# datalogger.net
KiCad netlist of a schematic drawn in Altium Designer
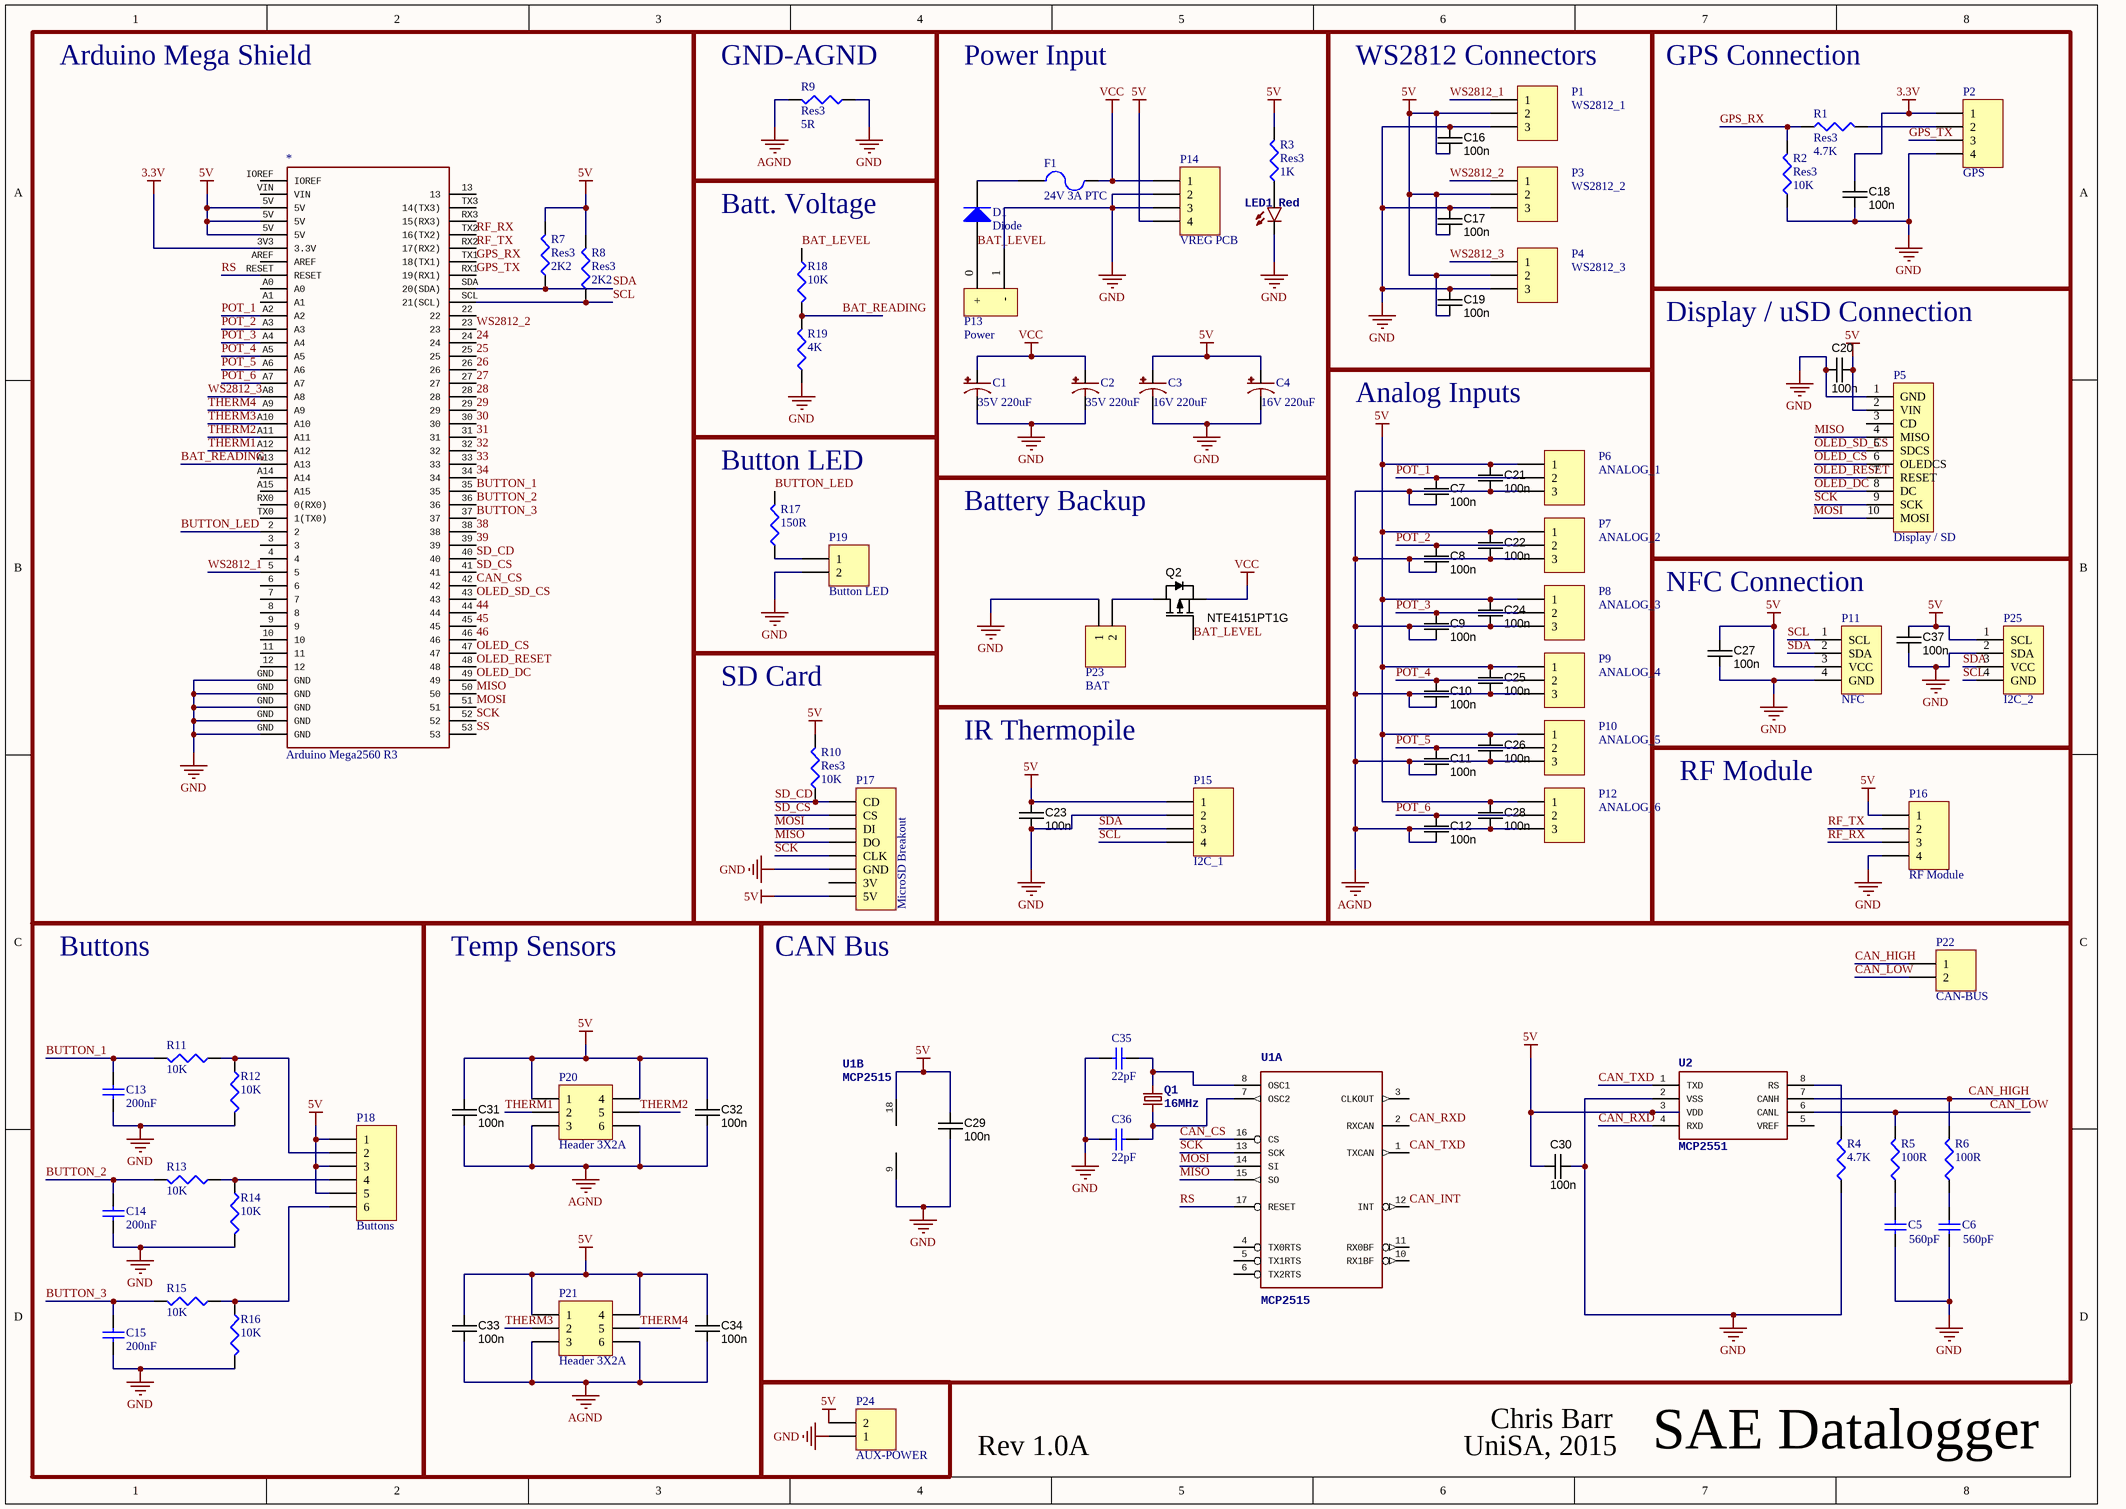
[diagram p0: datalogger.SchDoc]

(export (version "E")
  (design (tool "Eeschema 10.0.6"))
  (components
    (comp (ref "*")
      (value "Arduino Mega2560 R3")
      (footprint "Arduino Mega Shield - No Text")
      (libsource (lib "Schlib1") (part "Arduino Mega2560 R3"))
    )
    (comp (ref "C1")
      (value "35V 220uF")
      (footprint "8-DIA-CAP-3.5mm-Leads")
      (libsource (lib "Schlib1") (part "Capacitor 50V 470uF"))
    )
    (comp (ref "C2")
      (value "35V 220uF")
      (footprint "8-DIA-CAP-3.5mm-Leads")
      (libsource (lib "Schlib1") (part "Capacitor 50V 470uF"))
    )
    (comp (ref "C3")
      (value "16V 220uF")
      (footprint "6.3-DIA-CAP")
      (libsource (lib "Schlib1") (part "Capacitor 50V 470uF"))
    )
    (comp (ref "C4")
      (value "16V 220uF")
      (footprint "6.3-DIA-CAP")
      (libsource (lib "Schlib1") (part "Capacitor 50V 470uF"))
    )
    (comp (ref "C5")
      (value "560pF")
      (footprint "1608[0603]")
      (description "Capacitor (Semiconductor SIM Model)")
      (fields (field (name "Comment") "Cap Ceramic") (field (name "PUBLISHER") "Altium Limited"))
      (libsource (lib "Miscellaneous Devices") (part "Cap Semi"))
    )
    (comp (ref "C6")
      (value "560pF")
      (footprint "1608[0603]")
      (description "Capacitor (Semiconductor SIM Model)")
      (fields (field (name "Comment") "Cap Ceramic") (field (name "PUBLISHER") "Altium Limited"))
      (libsource (lib "Miscellaneous Devices") (part "Cap Semi"))
    )
    (comp (ref "C7")
      (value "100n")
      (footprint "CAPC1608X90N")
      (description "Capacitor SMD Cer 100nF 10% 50V X7R 0603")
      (fields (field (name "TOLERANCE") "±10%") (field (name "Comment") "approved sub OK"))
      (libsource (lib "PBL - Capacitors") (part "CAPC_100n_0603_X7R_50V_10%"))
    )
    (comp (ref "C8")
      (value "100n")
      (footprint "CAPC1608X90N")
      (description "Capacitor SMD Cer 100nF 10% 50V X7R 0603")
      (fields (field (name "TOLERANCE") "±10%") (field (name "Comment") "approved sub OK"))
      (libsource (lib "PBL - Capacitors") (part "CAPC_100n_0603_X7R_50V_10%"))
    )
    (comp (ref "C9")
      (value "100n")
      (footprint "CAPC1608X90N")
      (description "Capacitor SMD Cer 100nF 10% 50V X7R 0603")
      (fields (field (name "TOLERANCE") "±10%") (field (name "Comment") "approved sub OK"))
      (libsource (lib "PBL - Capacitors") (part "CAPC_100n_0603_X7R_50V_10%"))
    )
    (comp (ref "C10")
      (value "100n")
      (footprint "CAPC1608X90N")
      (description "Capacitor SMD Cer 100nF 10% 50V X7R 0603")
      (fields (field (name "TOLERANCE") "±10%") (field (name "Comment") "approved sub OK"))
      (libsource (lib "PBL - Capacitors") (part "CAPC_100n_0603_X7R_50V_10%"))
    )
    (comp (ref "C11")
      (value "100n")
      (footprint "CAPC1608X90N")
      (description "Capacitor SMD Cer 100nF 10% 50V X7R 0603")
      (fields (field (name "TOLERANCE") "±10%") (field (name "Comment") "approved sub OK"))
      (libsource (lib "PBL - Capacitors") (part "CAPC_100n_0603_X7R_50V_10%"))
    )
    (comp (ref "C12")
      (value "100n")
      (footprint "CAPC1608X90N")
      (description "Capacitor SMD Cer 100nF 10% 50V X7R 0603")
      (fields (field (name "TOLERANCE") "±10%") (field (name "Comment") "approved sub OK"))
      (libsource (lib "PBL - Capacitors") (part "CAPC_100n_0603_X7R_50V_10%"))
    )
    (comp (ref "C13")
      (value "200nF")
      (footprint "1608[0603]")
      (description "Capacitor (Semiconductor SIM Model)")
      (fields (field (name "Comment") "Cap Ceramic") (field (name "PUBLISHER") "Altium Limited"))
      (libsource (lib "Miscellaneous Devices") (part "Cap Semi"))
    )
    (comp (ref "C14")
      (value "200nF")
      (footprint "1608[0603]")
      (description "Capacitor (Semiconductor SIM Model)")
      (fields (field (name "Comment") "Cap Ceramic") (field (name "PUBLISHER") "Altium Limited"))
      (libsource (lib "Miscellaneous Devices") (part "Cap Semi"))
    )
    (comp (ref "C15")
      (value "200nF")
      (footprint "1608[0603]")
      (description "Capacitor (Semiconductor SIM Model)")
      (fields (field (name "Comment") "Cap Ceramic") (field (name "PUBLISHER") "Altium Limited"))
      (libsource (lib "Miscellaneous Devices") (part "Cap Semi"))
    )
    (comp (ref "C16")
      (value "100n")
      (footprint "CAPC1608X90N")
      (description "Capacitor SMD Cer 100nF 10% 50V X7R 0603")
      (fields (field (name "TOLERANCE") "±10%") (field (name "Comment") "approved sub OK"))
      (libsource (lib "PBL - Capacitors") (part "CAPC_100n_0603_X7R_50V_10%"))
    )
    (comp (ref "C17")
      (value "100n")
      (footprint "CAPC1608X90N")
      (description "Capacitor SMD Cer 100nF 10% 50V X7R 0603")
      (fields (field (name "TOLERANCE") "±10%") (field (name "Comment") "approved sub OK"))
      (libsource (lib "PBL - Capacitors") (part "CAPC_100n_0603_X7R_50V_10%"))
    )
    (comp (ref "C18")
      (value "100n")
      (footprint "CAPC1608X90N")
      (description "Capacitor SMD Cer 100nF 10% 50V X7R 0603")
      (fields (field (name "TOLERANCE") "±10%") (field (name "Comment") "approved sub OK"))
      (libsource (lib "PBL - Capacitors") (part "CAPC_100n_0603_X7R_50V_10%"))
    )
    (comp (ref "C19")
      (value "100n")
      (footprint "CAPC1608X90N")
      (description "Capacitor SMD Cer 100nF 10% 50V X7R 0603")
      (fields (field (name "TOLERANCE") "±10%") (field (name "Comment") "approved sub OK"))
      (libsource (lib "PBL - Capacitors") (part "CAPC_100n_0603_X7R_50V_10%"))
    )
    (comp (ref "C20")
      (value "100n")
      (footprint "CAPC1608X90N")
      (description "Capacitor SMD Cer 100nF 10% 50V X7R 0603")
      (fields (field (name "TOLERANCE") "±10%") (field (name "Comment") "approved sub OK"))
      (libsource (lib "PBL - Capacitors") (part "CAPC_100n_0603_X7R_50V_10%"))
    )
    (comp (ref "C21")
      (value "100n")
      (footprint "CAPC1608X90N")
      (description "Capacitor SMD Cer 100nF 10% 50V X7R 0603")
      (fields (field (name "TOLERANCE") "±10%") (field (name "Comment") "approved sub OK"))
      (libsource (lib "PBL - Capacitors") (part "CAPC_100n_0603_X7R_50V_10%"))
    )
    (comp (ref "C22")
      (value "100n")
      (footprint "CAPC1608X90N")
      (description "Capacitor SMD Cer 100nF 10% 50V X7R 0603")
      (fields (field (name "TOLERANCE") "±10%") (field (name "Comment") "approved sub OK"))
      (libsource (lib "PBL - Capacitors") (part "CAPC_100n_0603_X7R_50V_10%"))
    )
    (comp (ref "C23")
      (value "100n")
      (footprint "CAPC1608X90N")
      (description "Capacitor SMD Cer 100nF 10% 50V X7R 0603")
      (fields (field (name "TOLERANCE") "±10%") (field (name "Comment") "approved sub OK"))
      (libsource (lib "PBL - Capacitors") (part "CAPC_100n_0603_X7R_50V_10%"))
    )
    (comp (ref "C24")
      (value "100n")
      (footprint "CAPC1608X90N")
      (description "Capacitor SMD Cer 100nF 10% 50V X7R 0603")
      (fields (field (name "TOLERANCE") "±10%") (field (name "Comment") "approved sub OK"))
      (libsource (lib "PBL - Capacitors") (part "CAPC_100n_0603_X7R_50V_10%"))
    )
    (comp (ref "C25")
      (value "100n")
      (footprint "CAPC1608X90N")
      (description "Capacitor SMD Cer 100nF 10% 50V X7R 0603")
      (fields (field (name "TOLERANCE") "±10%") (field (name "Comment") "approved sub OK"))
      (libsource (lib "PBL - Capacitors") (part "CAPC_100n_0603_X7R_50V_10%"))
    )
    (comp (ref "C26")
      (value "100n")
      (footprint "CAPC1608X90N")
      (description "Capacitor SMD Cer 100nF 10% 50V X7R 0603")
      (fields (field (name "TOLERANCE") "±10%") (field (name "Comment") "approved sub OK"))
      (libsource (lib "PBL - Capacitors") (part "CAPC_100n_0603_X7R_50V_10%"))
    )
    (comp (ref "C27")
      (value "100n")
      (footprint "CAPC1608X90N")
      (description "Capacitor SMD Cer 100nF 10% 50V X7R 0603")
      (fields (field (name "TOLERANCE") "±10%") (field (name "Comment") "approved sub OK"))
      (libsource (lib "PBL - Capacitors") (part "CAPC_100n_0603_X7R_50V_10%"))
    )
    (comp (ref "C28")
      (value "100n")
      (footprint "CAPC1608X90N")
      (description "Capacitor SMD Cer 100nF 10% 50V X7R 0603")
      (fields (field (name "TOLERANCE") "±10%") (field (name "Comment") "approved sub OK"))
      (libsource (lib "PBL - Capacitors") (part "CAPC_100n_0603_X7R_50V_10%"))
    )
    (comp (ref "C29")
      (value "100n")
      (footprint "CAPC1608X90N")
      (description "Capacitor SMD Cer 100nF 10% 50V X7R 0603")
      (fields (field (name "TOLERANCE") "±10%") (field (name "Comment") "approved sub OK"))
      (libsource (lib "PBL - Capacitors") (part "CAPC_100n_0603_X7R_50V_10%"))
    )
    (comp (ref "C30")
      (value "100n")
      (footprint "CAPC1608X90N")
      (description "Capacitor SMD Cer 100nF 10% 50V X7R 0603")
      (fields (field (name "TOLERANCE") "±10%") (field (name "Comment") "approved sub OK"))
      (libsource (lib "PBL - Capacitors") (part "CAPC_100n_0603_X7R_50V_10%"))
    )
    (comp (ref "C31")
      (value "100n")
      (footprint "CAPC1608X90N")
      (description "Capacitor SMD Cer 100nF 10% 50V X7R 0603")
      (fields (field (name "TOLERANCE") "±10%") (field (name "Comment") "approved sub OK"))
      (libsource (lib "PBL - Capacitors") (part "CAPC_100n_0603_X7R_50V_10%"))
    )
    (comp (ref "C32")
      (value "100n")
      (footprint "CAPC1608X90N")
      (description "Capacitor SMD Cer 100nF 10% 50V X7R 0603")
      (fields (field (name "TOLERANCE") "±10%") (field (name "Comment") "approved sub OK"))
      (libsource (lib "PBL - Capacitors") (part "CAPC_100n_0603_X7R_50V_10%"))
    )
    (comp (ref "C33")
      (value "100n")
      (footprint "CAPC1608X90N")
      (description "Capacitor SMD Cer 100nF 10% 50V X7R 0603")
      (fields (field (name "TOLERANCE") "±10%") (field (name "Comment") "approved sub OK"))
      (libsource (lib "PBL - Capacitors") (part "CAPC_100n_0603_X7R_50V_10%"))
    )
    (comp (ref "C34")
      (value "100n")
      (footprint "CAPC1608X90N")
      (description "Capacitor SMD Cer 100nF 10% 50V X7R 0603")
      (fields (field (name "TOLERANCE") "±10%") (field (name "Comment") "approved sub OK"))
      (libsource (lib "PBL - Capacitors") (part "CAPC_100n_0603_X7R_50V_10%"))
    )
    (comp (ref "C35")
      (value "22pF")
      (footprint "1608[0603]")
      (description "Capacitor (Semiconductor SIM Model)")
      (fields (field (name "Comment") "Cap Ceramic") (field (name "PUBLISHER") "Altium Limited"))
      (libsource (lib "Miscellaneous Devices") (part "Cap Semi"))
    )
    (comp (ref "C36")
      (value "22pF")
      (footprint "1608[0603]")
      (description "Capacitor (Semiconductor SIM Model)")
      (fields (field (name "Comment") "Cap Ceramic") (field (name "PUBLISHER") "Altium Limited"))
      (libsource (lib "Miscellaneous Devices") (part "Cap Semi"))
    )
    (comp (ref "C37")
      (value "100n")
      (footprint "CAPC1608X90N")
      (description "Capacitor SMD Cer 100nF 10% 50V X7R 0603")
      (fields (field (name "TOLERANCE") "±10%") (field (name "Comment") "approved sub OK"))
      (libsource (lib "PBL - Capacitors") (part "CAPC_100n_0603_X7R_50V_10%"))
    )
    (comp (ref "D1")
      (value "Diode")
      (footprint "SMC")
      (description "Default Diode")
      (fields (field (name "PUBLISHER") "Altium Limited"))
      (libsource (lib "Miscellaneous Devices") (part "Diode"))
    )
    (comp (ref "F1")
      (value "24V 3A PTC")
      (footprint "MF-LSMF SMD PTC Fuse")
      (description "Fuse")
      (fields (field (name "PUBLISHER") "Altium Limited"))
      (libsource (lib "Miscellaneous Devices") (part "Fuse 2"))
    )
    (comp (ref "LED1")
      (value "Red")
      (footprint "LED-0603")
      (description "Power Indicator")
      (libsource (lib "SparkFun-LED") (part "LED0603"))
    )
    (comp (ref "P1")
      (value "WS2812_1")
      (footprint "HDR1X3")
      (description "Header, 3-Pin")
      (fields (field (name "PUBLISHER") "Altium Limited"))
      (libsource (lib "Miscellaneous Connectors") (part "Header 3"))
    )
    (comp (ref "P2")
      (value "GPS")
      (footprint "HDR1X4")
      (description "Header, 4-Pin")
      (fields (field (name "PUBLISHER") "Altium Limited"))
      (libsource (lib "") (part "Header 4_1"))
    )
    (comp (ref "P3")
      (value "WS2812_2")
      (footprint "HDR1X3")
      (description "Header, 3-Pin")
      (fields (field (name "PUBLISHER") "Altium Limited"))
      (libsource (lib "Miscellaneous Connectors") (part "Header 3"))
    )
    (comp (ref "P4")
      (value "WS2812_3")
      (footprint "HDR1X3")
      (description "Header, 3-Pin")
      (fields (field (name "PUBLISHER") "Altium Limited"))
      (libsource (lib "Miscellaneous Connectors") (part "Header 3"))
    )
    (comp (ref "P5")
      (value "Display / SD")
      (footprint "HDR1X10")
      (description "Header, 10-Pin")
      (fields (field (name "PUBLISHER") "Altium Limited"))
      (libsource (lib "Miscellaneous Connectors") (part "Header 10"))
    )
    (comp (ref "P6")
      (value "ANALOG_1")
      (footprint "HDR1X3")
      (description "Header, 3-Pin")
      (fields (field (name "PUBLISHER") "Altium Limited"))
      (libsource (lib "Miscellaneous Connectors") (part "Header 3"))
    )
    (comp (ref "P7")
      (value "ANALOG_2")
      (footprint "HDR1X3")
      (description "Header, 3-Pin")
      (fields (field (name "PUBLISHER") "Altium Limited"))
      (libsource (lib "Miscellaneous Connectors") (part "Header 3"))
    )
    (comp (ref "P8")
      (value "ANALOG_3")
      (footprint "HDR1X3")
      (description "Header, 3-Pin")
      (fields (field (name "PUBLISHER") "Altium Limited"))
      (libsource (lib "Miscellaneous Connectors") (part "Header 3"))
    )
    (comp (ref "P9")
      (value "ANALOG_4")
      (footprint "HDR1X3")
      (description "Header, 3-Pin")
      (fields (field (name "PUBLISHER") "Altium Limited"))
      (libsource (lib "Miscellaneous Connectors") (part "Header 3"))
    )
    (comp (ref "P10")
      (value "ANALOG_5")
      (footprint "HDR1X3")
      (description "Header, 3-Pin")
      (fields (field (name "PUBLISHER") "Altium Limited"))
      (libsource (lib "Miscellaneous Connectors") (part "Header 3"))
    )
    (comp (ref "P11")
      (value "NFC")
      (footprint "HDR1X4")
      (description "Header, 4-Pin")
      (fields (field (name "PUBLISHER") "Altium Limited"))
      (libsource (lib "Miscellaneous Connectors") (part "Header 4"))
    )
    (comp (ref "P12")
      (value "ANALOG_6")
      (footprint "HDR1X3")
      (description "Header, 3-Pin")
      (fields (field (name "PUBLISHER") "Altium Limited"))
      (libsource (lib "Miscellaneous Connectors") (part "Header 3"))
    )
    (comp (ref "P13")
      (value "Power")
      (footprint "2P 5.08mm Screw Terminal")
      (libsource (lib "Schlib1") (part "2P Screw Terminal 5.08mm"))
    )
    (comp (ref "P14")
      (value "VREG PCB")
      (footprint "HDR1X4")
      (description "Header, 4-Pin")
      (fields (field (name "PUBLISHER") "Altium Limited"))
      (libsource (lib "") (part "Header 4_1"))
    )
    (comp (ref "P15")
      (value "I2C_1")
      (footprint "HDR1X4")
      (description "Header, 4-Pin")
      (fields (field (name "PUBLISHER") "Altium Limited"))
      (libsource (lib "") (part "Header 4_1"))
    )
    (comp (ref "P16")
      (value "RF Module")
      (footprint "HDR1X4")
      (description "Header, 4-Pin")
      (fields (field (name "PUBLISHER") "Altium Limited"))
      (libsource (lib "") (part "Header 4_1"))
    )
    (comp (ref "P17")
      (value "MicroSD Breakout")
      (footprint "HDR1X8")
      (description "Header, 8-Pin")
      (fields (field (name "PUBLISHER") "Altium Limited"))
      (libsource (lib "Miscellaneous Connectors") (part "Header 8"))
    )
    (comp (ref "P18")
      (value "Buttons")
      (footprint "HDR1X6")
      (description "Header, 6-Pin")
      (fields (field (name "PUBLISHER") "Altium Limited"))
      (libsource (lib "Miscellaneous Connectors") (part "Header 6"))
    )
    (comp (ref "P19")
      (value "Button LED")
      (footprint "HDR1X2")
      (description "Header, 2-Pin")
      (fields (field (name "PUBLISHER") "Altium Limited"))
      (libsource (lib "Miscellaneous Connectors") (part "Header 2"))
    )
    (comp (ref "P20")
      (value "Header 3X2A")
      (footprint "HDR2X3_CEN")
      (description "Header, 3-Pin, Dual row")
      (fields (field (name "PUBLISHER") "Altium Limited"))
      (libsource (lib "Miscellaneous Connectors") (part "Header 3X2A"))
    )
    (comp (ref "P21")
      (value "Header 3X2A")
      (footprint "HDR2X3_CEN")
      (description "Header, 3-Pin, Dual row")
      (fields (field (name "PUBLISHER") "Altium Limited"))
      (libsource (lib "Miscellaneous Connectors") (part "Header 3X2A"))
    )
    (comp (ref "P22")
      (value "CAN-BUS")
      (footprint "HDR1X2")
      (description "Header, 2-Pin")
      (fields (field (name "PUBLISHER") "Altium Limited"))
      (libsource (lib "Miscellaneous Connectors") (part "Header 2"))
    )
    (comp (ref "P23")
      (value "BAT")
      (footprint "HDR1X2")
      (description "Header, 2-Pin")
      (fields (field (name "PUBLISHER") "Altium Limited"))
      (libsource (lib "") (part "Header 2_1"))
    )
    (comp (ref "P24")
      (value "AUX-POWER")
      (footprint "HDR1X2")
      (description "Header, 2-Pin")
      (fields (field (name "PUBLISHER") "Altium Limited"))
      (libsource (lib "") (part "Header 2_2"))
    )
    (comp (ref "P25")
      (value "I2C_2")
      (footprint "HDR1X4")
      (description "Header, 4-Pin")
      (fields (field (name "PUBLISHER") "Altium Limited"))
      (libsource (lib "Miscellaneous Connectors") (part "Header 4"))
    )
    (comp (ref "Q1")
      (value "16MHz")
      (footprint "HC-46X")
      (libsource (lib "SparkFun-FreqCtrl") (part "CRYSTALHC49US"))
    )
    (comp (ref "Q2")
      (value "P-Channel")
      (footprint "SOT23-3")
      (description "MOSFET SMD P-CH 20V 0.76A 0.313W SOT523F")
      (fields (field (name "MANUFACTURER PART NUMBER 1") "NTE4151PT1G"))
      (libsource (lib "PBL - Transistors") (part "MOSFET_P-CH_NTE4151PT1G"))
    )
    (comp (ref "R1")
      (value "Res3")
      (footprint "J1-0603")
      (description "Resistor")
      (fields (field (name "ALTIUM_VALUE") "4.7K") (field (name "PUBLISHER") "Altium Limited"))
      (libsource (lib "Miscellaneous Devices") (part "Res3"))
    )
    (comp (ref "R2")
      (value "Res3")
      (footprint "J1-0603")
      (description "Resistor")
      (fields (field (name "ALTIUM_VALUE") "10K") (field (name "PUBLISHER") "Altium Limited"))
      (libsource (lib "Miscellaneous Devices") (part "Res3"))
    )
    (comp (ref "R3")
      (value "Res3")
      (footprint "J1-0603")
      (description "Resistor")
      (fields (field (name "ALTIUM_VALUE") "1K") (field (name "PUBLISHER") "Altium Limited"))
      (libsource (lib "Miscellaneous Devices") (part "Res3"))
    )
    (comp (ref "R4")
      (value "4.7K")
      (footprint "J1-0603")
      (description "Resistor")
      (fields (field (name "PUBLISHER") "Altium Limited"))
      (libsource (lib "Miscellaneous Devices") (part "Res3"))
    )
    (comp (ref "R5")
      (value "100R")
      (footprint "J1-0603")
      (description "Resistor")
      (fields (field (name "PUBLISHER") "Altium Limited"))
      (libsource (lib "Miscellaneous Devices") (part "Res3"))
    )
    (comp (ref "R6")
      (value "100R")
      (footprint "J1-0603")
      (description "Resistor")
      (fields (field (name "PUBLISHER") "Altium Limited"))
      (libsource (lib "Miscellaneous Devices") (part "Res3"))
    )
    (comp (ref "R7")
      (value "Res3")
      (footprint "J1-0603")
      (description "Resistor")
      (fields (field (name "ALTIUM_VALUE") "2K2") (field (name "PUBLISHER") "Altium Limited"))
      (libsource (lib "Miscellaneous Devices") (part "Res3"))
    )
    (comp (ref "R8")
      (value "Res3")
      (footprint "J1-0603")
      (description "Resistor")
      (fields (field (name "ALTIUM_VALUE") "2K2") (field (name "PUBLISHER") "Altium Limited"))
      (libsource (lib "Miscellaneous Devices") (part "Res3"))
    )
    (comp (ref "R9")
      (value "Res3")
      (footprint "0805")
      (description "Resistor")
      (fields (field (name "ALTIUM_VALUE") "5R") (field (name "PUBLISHER") "Altium Limited"))
      (libsource (lib "Miscellaneous Devices") (part "Res3"))
    )
    (comp (ref "R10")
      (value "Res3")
      (footprint "J1-0603")
      (description "Resistor")
      (fields (field (name "ALTIUM_VALUE") "10K") (field (name "PUBLISHER") "Altium Limited"))
      (libsource (lib "Miscellaneous Devices") (part "Res3"))
    )
    (comp (ref "R11")
      (value "10K")
      (footprint "J1-0603")
      (description "Resistor")
      (fields (field (name "PUBLISHER") "Altium Limited"))
      (libsource (lib "Miscellaneous Devices") (part "Res3"))
    )
    (comp (ref "R12")
      (value "10K")
      (footprint "J1-0603")
      (description "Resistor")
      (fields (field (name "PUBLISHER") "Altium Limited"))
      (libsource (lib "Miscellaneous Devices") (part "Res3"))
    )
    (comp (ref "R13")
      (value "10K")
      (footprint "J1-0603")
      (description "Resistor")
      (fields (field (name "PUBLISHER") "Altium Limited"))
      (libsource (lib "Miscellaneous Devices") (part "Res3"))
    )
    (comp (ref "R14")
      (value "10K")
      (footprint "J1-0603")
      (description "Resistor")
      (fields (field (name "PUBLISHER") "Altium Limited"))
      (libsource (lib "Miscellaneous Devices") (part "Res3"))
    )
    (comp (ref "R15")
      (value "10K")
      (footprint "J1-0603")
      (description "Resistor")
      (fields (field (name "PUBLISHER") "Altium Limited"))
      (libsource (lib "Miscellaneous Devices") (part "Res3"))
    )
    (comp (ref "R16")
      (value "10K")
      (footprint "J1-0603")
      (description "Resistor")
      (fields (field (name "PUBLISHER") "Altium Limited"))
      (libsource (lib "Miscellaneous Devices") (part "Res3"))
    )
    (comp (ref "R17")
      (value "150R")
      (footprint "J1-0603")
      (description "Resistor")
      (fields (field (name "PUBLISHER") "Altium Limited"))
      (libsource (lib "Miscellaneous Devices") (part "Res3"))
    )
    (comp (ref "R18")
      (value "10K")
      (footprint "J1-0603")
      (description "Resistor")
      (fields (field (name "PUBLISHER") "Altium Limited"))
      (libsource (lib "Miscellaneous Devices") (part "Res3"))
    )
    (comp (ref "R19")
      (value "4K")
      (footprint "J1-0603")
      (description "Resistor")
      (fields (field (name "PUBLISHER") "Altium Limited"))
      (libsource (lib "Miscellaneous Devices") (part "Res3"))
    )
    (comp (ref "U1")
      (value "MCP2515")
      (footprint "SO-18W")
      (libsource (lib "CAN-Bus_Shield") (part "MCP2510SO"))
    )
    (comp (ref "U2")
      (value "MCP2551")
      (footprint "SO08")
      (libsource (lib "SparkFun-DigitalIC") (part "MCP2551"))
    )
  )
  (nets
    (net (code "1") (name "/24") (class "Default")
      (node (ref "*") (pin "24") (pinfunction "24_24") (pintype "passive"))
    )
    (net (code "2") (name "/25") (class "Default")
      (node (ref "*") (pin "25") (pinfunction "25_25") (pintype "passive"))
    )
    (net (code "3") (name "/26") (class "Default")
      (node (ref "*") (pin "26") (pinfunction "26_26") (pintype "passive"))
    )
    (net (code "4") (name "/27") (class "Default")
      (node (ref "*") (pin "27") (pinfunction "27_27") (pintype "passive"))
    )
    (net (code "5") (name "/28") (class "Default")
      (node (ref "*") (pin "28") (pinfunction "28_28") (pintype "passive"))
    )
    (net (code "6") (name "/29") (class "Default")
      (node (ref "*") (pin "29") (pinfunction "29_29") (pintype "passive"))
    )
    (net (code "7") (name "/30") (class "Default")
      (node (ref "*") (pin "30") (pinfunction "30_30") (pintype "passive"))
    )
    (net (code "8") (name "/31") (class "Default")
      (node (ref "*") (pin "31") (pinfunction "31_31") (pintype "passive"))
    )
    (net (code "9") (name "/32") (class "Default")
      (node (ref "*") (pin "32") (pinfunction "32_32") (pintype "passive"))
    )
    (net (code "10") (name "/33") (class "Default")
      (node (ref "*") (pin "33") (pinfunction "33_33") (pintype "passive"))
    )
    (net (code "11") (name "/34") (class "Default")
      (node (ref "*") (pin "34") (pinfunction "34_34") (pintype "passive"))
    )
    (net (code "12") (name "/38") (class "Default")
      (node (ref "*") (pin "38") (pinfunction "38_38") (pintype "passive"))
    )
    (net (code "13") (name "/39") (class "Default")
      (node (ref "*") (pin "39") (pinfunction "39_39") (pintype "passive"))
    )
    (net (code "14") (name "/44") (class "Default")
      (node (ref "*") (pin "44") (pinfunction "44_44") (pintype "passive"))
    )
    (net (code "15") (name "/45") (class "Default")
      (node (ref "*") (pin "45") (pinfunction "45_45") (pintype "passive"))
    )
    (net (code "16") (name "/46") (class "Default")
      (node (ref "*") (pin "46") (pinfunction "46_46") (pintype "passive"))
    )
    (net (code "17") (name "/BAT_LEVEL") (class "Default")
      (node (ref "D1") (pin "1") (pinfunction "A_1") (pintype "passive"))
      (node (ref "P13") (pin "0") (pinfunction "+_0") (pintype "passive"))
      (node (ref "Q2") (pin "1") (pinfunction "G_1") (pintype "passive"))
      (node (ref "R18") (pin "1") (pinfunction "1_1") (pintype "passive"))
    )
    (net (code "18") (name "/BAT_READING") (class "Default")
      (node (ref "*") (pin "A13") (pinfunction "A13_A13") (pintype "passive"))
      (node (ref "R18") (pin "2") (pinfunction "2_2") (pintype "passive"))
      (node (ref "R19") (pin "2") (pinfunction "2_2") (pintype "passive"))
    )
    (net (code "19") (name "/BUTTON_1") (class "Default")
      (node (ref "*") (pin "35") (pinfunction "35_35") (pintype "passive"))
      (node (ref "C13") (pin "1") (pinfunction "1_1") (pintype "passive"))
      (node (ref "R11") (pin "2") (pinfunction "2_2") (pintype "passive"))
    )
    (net (code "20") (name "/BUTTON_2") (class "Default")
      (node (ref "*") (pin "36") (pinfunction "36_36") (pintype "passive"))
      (node (ref "C14") (pin "1") (pinfunction "1_1") (pintype "passive"))
      (node (ref "R13") (pin "2") (pinfunction "2_2") (pintype "passive"))
    )
    (net (code "21") (name "/BUTTON_3") (class "Default")
      (node (ref "*") (pin "37") (pinfunction "37_37") (pintype "passive"))
      (node (ref "C15") (pin "1") (pinfunction "1_1") (pintype "passive"))
      (node (ref "R15") (pin "2") (pinfunction "2_2") (pintype "passive"))
    )
    (net (code "22") (name "/BUTTON_LED") (class "Default")
      (node (ref "*") (pin "2") (pinfunction "2_2") (pintype "passive"))
      (node (ref "R17") (pin "2") (pinfunction "2_2") (pintype "passive"))
    )
    (net (code "23") (name "/CAN_CS") (class "Default")
      (node (ref "*") (pin "42") (pinfunction "42_42") (pintype "passive"))
      (node (ref "U1") (pin "16") (pinfunction "CS_16") (pintype "passive"))
    )
    (net (code "24") (name "/CAN_HIGH") (class "Default")
      (node (ref "P22") (pin "1") (pinfunction "1_1") (pintype "passive"))
      (node (ref "R6") (pin "2") (pinfunction "2_2") (pintype "passive"))
      (node (ref "U2") (pin "7") (pinfunction "CANH_7") (pintype "passive"))
    )
    (net (code "25") (name "/CAN_INT") (class "Default")
      (node (ref "U1") (pin "12") (pinfunction "INT_12") (pintype "output"))
    )
    (net (code "26") (name "/CAN_LOW") (class "Default")
      (node (ref "P22") (pin "2") (pinfunction "2_2") (pintype "passive"))
      (node (ref "R5") (pin "2") (pinfunction "2_2") (pintype "passive"))
      (node (ref "U2") (pin "6") (pinfunction "CANL_6") (pintype "passive"))
    )
    (net (code "27") (name "/CAN_RXD") (class "Default")
      (node (ref "U1") (pin "2") (pinfunction "RXCAN_2") (pintype "passive"))
      (node (ref "U2") (pin "4") (pinfunction "RXD_4") (pintype "passive"))
    )
    (net (code "28") (name "/CAN_TXD") (class "Default")
      (node (ref "U1") (pin "1") (pinfunction "TXCAN_1") (pintype "output"))
      (node (ref "U2") (pin "1") (pinfunction "TXD_1") (pintype "passive"))
    )
    (net (code "29") (name "/GPS_RX") (class "Default")
      (node (ref "*") (pin "TX1") (pinfunction "18(TX1)_TX1") (pintype "passive"))
      (node (ref "R1") (pin "1") (pinfunction "1_1") (pintype "passive"))
      (node (ref "R2") (pin "2") (pinfunction "2_2") (pintype "passive"))
    )
    (net (code "30") (name "/GPS_TX") (class "Default")
      (node (ref "*") (pin "RX1") (pinfunction "19(RX1)_RX1") (pintype "passive"))
      (node (ref "P2") (pin "3") (pinfunction "3_3") (pintype "passive"))
    )
    (net (code "31") (name "/MISO") (class "Default")
      (node (ref "*") (pin "50") (pinfunction "50_50") (pintype "passive"))
      (node (ref "P17") (pin "4") (pinfunction "DO_4") (pintype "passive"))
      (node (ref "P5") (pin "4") (pinfunction "MISO_4") (pintype "passive"))
      (node (ref "U1") (pin "15") (pinfunction "SO_15") (pintype "output"))
    )
    (net (code "32") (name "/MOSI") (class "Default")
      (node (ref "*") (pin "51") (pinfunction "51_51") (pintype "passive"))
      (node (ref "P17") (pin "3") (pinfunction "DI_3") (pintype "passive"))
      (node (ref "P5") (pin "10") (pinfunction "MOSI_10") (pintype "passive"))
      (node (ref "U1") (pin "14") (pinfunction "SI_14") (pintype "passive"))
    )
    (net (code "33") (name "/OLED_CS") (class "Default")
      (node (ref "*") (pin "47") (pinfunction "47_47") (pintype "passive"))
      (node (ref "P5") (pin "6") (pinfunction "OLEDCS_6") (pintype "passive"))
    )
    (net (code "34") (name "/OLED_DC") (class "Default")
      (node (ref "*") (pin "49") (pinfunction "49_49") (pintype "passive"))
      (node (ref "P5") (pin "8") (pinfunction "DC_8") (pintype "passive"))
    )
    (net (code "35") (name "/OLED_RESET") (class "Default")
      (node (ref "*") (pin "48") (pinfunction "48_48") (pintype "passive"))
      (node (ref "P5") (pin "7") (pinfunction "RESET_7") (pintype "passive"))
    )
    (net (code "36") (name "/OLED_SD_CS") (class "Default")
      (node (ref "*") (pin "43") (pinfunction "43_43") (pintype "passive"))
      (node (ref "P5") (pin "5") (pinfunction "SDCS_5") (pintype "passive"))
    )
    (net (code "37") (name "/POT_1") (class "Default")
      (node (ref "*") (pin "A2") (pinfunction "A2_A2") (pintype "passive"))
      (node (ref "C7") (pin "1") (pintype "passive"))
      (node (ref "P6") (pin "2") (pinfunction "2_2") (pintype "passive"))
    )
    (net (code "38") (name "/POT_2") (class "Default")
      (node (ref "*") (pin "A3") (pinfunction "A3_A3") (pintype "passive"))
      (node (ref "C8") (pin "1") (pintype "passive"))
      (node (ref "P7") (pin "2") (pinfunction "2_2") (pintype "passive"))
    )
    (net (code "39") (name "/POT_3") (class "Default")
      (node (ref "*") (pin "A4") (pinfunction "A4_A4") (pintype "passive"))
      (node (ref "C9") (pin "1") (pintype "passive"))
      (node (ref "P8") (pin "2") (pinfunction "2_2") (pintype "passive"))
    )
    (net (code "40") (name "/POT_4") (class "Default")
      (node (ref "*") (pin "A5") (pinfunction "A5_A5") (pintype "passive"))
      (node (ref "C10") (pin "1") (pintype "passive"))
      (node (ref "P9") (pin "2") (pinfunction "2_2") (pintype "passive"))
    )
    (net (code "41") (name "/POT_5") (class "Default")
      (node (ref "*") (pin "A6") (pinfunction "A6_A6") (pintype "passive"))
      (node (ref "C11") (pin "1") (pintype "passive"))
      (node (ref "P10") (pin "2") (pinfunction "2_2") (pintype "passive"))
    )
    (net (code "42") (name "/POT_6") (class "Default")
      (node (ref "*") (pin "A7") (pinfunction "A7_A7") (pintype "passive"))
      (node (ref "C12") (pin "1") (pintype "passive"))
      (node (ref "P12") (pin "2") (pinfunction "2_2") (pintype "passive"))
    )
    (net (code "43") (name "/RF_RX") (class "Default")
      (node (ref "*") (pin "TX2") (pinfunction "16(TX2)_TX2") (pintype "passive"))
      (node (ref "P16") (pin "3") (pinfunction "3_3") (pintype "passive"))
    )
    (net (code "44") (name "/RF_TX") (class "Default")
      (node (ref "*") (pin "RX2") (pinfunction "17(RX2)_RX2") (pintype "passive"))
      (node (ref "P16") (pin "2") (pinfunction "2_2") (pintype "passive"))
    )
    (net (code "45") (name "/RS") (class "Default")
      (node (ref "*") (pin "RESET") (pinfunction "RESET_RESET") (pintype "passive"))
      (node (ref "U1") (pin "17") (pinfunction "RESET_17") (pintype "passive"))
    )
    (net (code "46") (name "/SCK") (class "Default")
      (node (ref "*") (pin "52") (pinfunction "52_52") (pintype "passive"))
      (node (ref "P17") (pin "5") (pinfunction "CLK_5") (pintype "passive"))
      (node (ref "P5") (pin "9") (pinfunction "SCK_9") (pintype "passive"))
      (node (ref "U1") (pin "13") (pinfunction "SCK_13") (pintype "passive"))
    )
    (net (code "47") (name "/SCL") (class "Default")
      (node (ref "*") (pin "SCL") (pinfunction "21(SCL)_SCL") (pintype "passive"))
      (node (ref "P11") (pin "1") (pinfunction "SCL_1") (pintype "passive"))
      (node (ref "P15") (pin "4") (pinfunction "4_4") (pintype "passive"))
      (node (ref "P25") (pin "4") (pinfunction "GND_4") (pintype "passive"))
      (node (ref "R8") (pin "1") (pinfunction "1_1") (pintype "passive"))
    )
    (net (code "48") (name "/SDA") (class "Default")
      (node (ref "*") (pin "SDA") (pinfunction "20(SDA)_SDA") (pintype "passive"))
      (node (ref "P11") (pin "2") (pinfunction "SDA_2") (pintype "passive"))
      (node (ref "P15") (pin "3") (pinfunction "3_3") (pintype "passive"))
      (node (ref "P25") (pin "3") (pinfunction "VCC_3") (pintype "passive"))
      (node (ref "R7") (pin "1") (pinfunction "1_1") (pintype "passive"))
    )
    (net (code "49") (name "/SD_CD") (class "Default")
      (node (ref "*") (pin "40") (pinfunction "40_40") (pintype "passive"))
      (node (ref "P17") (pin "1") (pinfunction "CD_1") (pintype "passive"))
      (node (ref "R10") (pin "1") (pinfunction "1_1") (pintype "passive"))
    )
    (net (code "50") (name "/SD_CS") (class "Default")
      (node (ref "*") (pin "41") (pinfunction "41_41") (pintype "passive"))
      (node (ref "P17") (pin "2") (pinfunction "CS_2") (pintype "passive"))
    )
    (net (code "51") (name "/SS") (class "Default")
      (node (ref "*") (pin "53") (pinfunction "53_53") (pintype "passive"))
    )
    (net (code "52") (name "/THERM1") (class "Default")
      (node (ref "*") (pin "A12") (pinfunction "A12_A12") (pintype "passive"))
      (node (ref "P20") (pin "2") (pinfunction "2_2") (pintype "passive"))
    )
    (net (code "53") (name "/THERM2") (class "Default")
      (node (ref "*") (pin "A11") (pinfunction "A11_A11") (pintype "passive"))
      (node (ref "P20") (pin "5") (pinfunction "5_5") (pintype "passive"))
    )
    (net (code "54") (name "/THERM3") (class "Default")
      (node (ref "*") (pin "A10") (pinfunction "A10_A10") (pintype "passive"))
      (node (ref "P21") (pin "2") (pinfunction "2_2") (pintype "passive"))
    )
    (net (code "55") (name "/THERM4") (class "Default")
      (node (ref "*") (pin "A9") (pinfunction "A9_A9") (pintype "passive"))
      (node (ref "P21") (pin "5") (pinfunction "5_5") (pintype "passive"))
    )
    (net (code "56") (name "/WS2812_1") (class "Default")
      (node (ref "*") (pin "5") (pinfunction "5_5") (pintype "passive"))
      (node (ref "P1") (pin "1") (pinfunction "1_1") (pintype "passive"))
    )
    (net (code "57") (name "/WS2812_2") (class "Default")
      (node (ref "*") (pin "23") (pinfunction "23_23") (pintype "passive"))
      (node (ref "P3") (pin "1") (pinfunction "1_1") (pintype "passive"))
    )
    (net (code "58") (name "/WS2812_3") (class "Default")
      (node (ref "*") (pin "A8") (pinfunction "A8_A8") (pintype "passive"))
      (node (ref "P4") (pin "1") (pinfunction "1_1") (pintype "passive"))
    )
    (net (code "59") (name "3.3V") (class "Default")
      (node (ref "*") (pin "3V3") (pinfunction "3.3V_3V3") (pintype "passive"))
      (node (ref "C18") (pin "1") (pintype "passive"))
      (node (ref "P2") (pin "1") (pinfunction "1_1") (pintype "passive"))
    )
    (net (code "60") (name "5V") (class "Default")
      (node (ref "*") (pin "5V") (pinfunction "5V_5V") (pintype "passive"))
      (node (ref "C16") (pin "2") (pintype "passive"))
      (node (ref "C17") (pin "2") (pintype "passive"))
      (node (ref "C19") (pin "2") (pintype "passive"))
      (node (ref "C20") (pin "2") (pintype "passive"))
      (node (ref "C21") (pin "1") (pintype "passive"))
      (node (ref "C22") (pin "1") (pintype "passive"))
      (node (ref "C23") (pin "1") (pintype "passive"))
      (node (ref "C24") (pin "1") (pintype "passive"))
      (node (ref "C25") (pin "1") (pintype "passive"))
      (node (ref "C26") (pin "1") (pintype "passive"))
      (node (ref "C27") (pin "2") (pintype "passive"))
      (node (ref "C28") (pin "1") (pintype "passive"))
      (node (ref "C29") (pin "1") (pintype "passive"))
      (node (ref "C3") (pin "2") (pinfunction "+_2") (pintype "passive"))
      (node (ref "C30") (pin "2") (pintype "passive"))
      (node (ref "C31") (pin "1") (pintype "passive"))
      (node (ref "C32") (pin "1") (pintype "passive"))
      (node (ref "C33") (pin "1") (pintype "passive"))
      (node (ref "C34") (pin "1") (pintype "passive"))
      (node (ref "C37") (pin "2") (pintype "passive"))
      (node (ref "C4") (pin "2") (pinfunction "+_2") (pintype "passive"))
      (node (ref "P1") (pin "2") (pinfunction "2_2") (pintype "passive"))
      (node (ref "P10") (pin "1") (pinfunction "1_1") (pintype "passive"))
      (node (ref "P11") (pin "3") (pinfunction "VCC_3") (pintype "passive"))
      (node (ref "P12") (pin "1") (pinfunction "1_1") (pintype "passive"))
      (node (ref "P14") (pin "4") (pinfunction "4_4") (pintype "passive"))
      (node (ref "P15") (pin "1") (pinfunction "1_1") (pintype "passive"))
      (node (ref "P16") (pin "1") (pinfunction "1_1") (pintype "passive"))
      (node (ref "P17") (pin "8") (pinfunction "5V_8") (pintype "passive"))
      (node (ref "P18") (pin "1") (pinfunction "1_1") (pintype "passive"))
      (node (ref "P18") (pin "3") (pinfunction "3_3") (pintype "passive"))
      (node (ref "P18") (pin "5") (pinfunction "5_5") (pintype "passive"))
      (node (ref "P20") (pin "1") (pinfunction "1_1") (pintype "passive"))
      (node (ref "P20") (pin "4") (pinfunction "4_4") (pintype "passive"))
      (node (ref "P21") (pin "1") (pinfunction "1_1") (pintype "passive"))
      (node (ref "P21") (pin "4") (pinfunction "4_4") (pintype "passive"))
      (node (ref "P24") (pin "2") (pinfunction "2_2") (pintype "passive"))
      (node (ref "P25") (pin "1") (pinfunction "SCL_1") (pintype "passive"))
      (node (ref "P3") (pin "2") (pinfunction "2_2") (pintype "passive"))
      (node (ref "P4") (pin "2") (pinfunction "2_2") (pintype "passive"))
      (node (ref "P5") (pin "2") (pinfunction "VIN_2") (pintype "passive"))
      (node (ref "P6") (pin "1") (pinfunction "1_1") (pintype "passive"))
      (node (ref "P7") (pin "1") (pinfunction "1_1") (pintype "passive"))
      (node (ref "P8") (pin "1") (pinfunction "1_1") (pintype "passive"))
      (node (ref "P9") (pin "1") (pinfunction "1_1") (pintype "passive"))
      (node (ref "R10") (pin "2") (pinfunction "2_2") (pintype "passive"))
      (node (ref "R3") (pin "2") (pinfunction "2_2") (pintype "passive"))
      (node (ref "R7") (pin "2") (pinfunction "2_2") (pintype "passive"))
      (node (ref "R8") (pin "2") (pinfunction "2_2") (pintype "passive"))
      (node (ref "U1") (pin "18") (pinfunction "VDD_18") (pintype "power_in"))
      (node (ref "U2") (pin "3") (pinfunction "VDD_3") (pintype "passive"))
    )
    (net (code "61") (name "AGND") (class "Default")
      (node (ref "C10") (pin "2") (pintype "passive"))
      (node (ref "C11") (pin "2") (pintype "passive"))
      (node (ref "C12") (pin "2") (pintype "passive"))
      (node (ref "C21") (pin "2") (pintype "passive"))
      (node (ref "C22") (pin "2") (pintype "passive"))
      (node (ref "C24") (pin "2") (pintype "passive"))
      (node (ref "C25") (pin "2") (pintype "passive"))
      (node (ref "C26") (pin "2") (pintype "passive"))
      (node (ref "C28") (pin "2") (pintype "passive"))
      (node (ref "C31") (pin "2") (pintype "passive"))
      (node (ref "C32") (pin "2") (pintype "passive"))
      (node (ref "C33") (pin "2") (pintype "passive"))
      (node (ref "C34") (pin "2") (pintype "passive"))
      (node (ref "C7") (pin "2") (pintype "passive"))
      (node (ref "C8") (pin "2") (pintype "passive"))
      (node (ref "C9") (pin "2") (pintype "passive"))
      (node (ref "P10") (pin "3") (pinfunction "3_3") (pintype "passive"))
      (node (ref "P12") (pin "3") (pinfunction "3_3") (pintype "passive"))
      (node (ref "P20") (pin "3") (pinfunction "3_3") (pintype "passive"))
      (node (ref "P20") (pin "6") (pinfunction "6_6") (pintype "passive"))
      (node (ref "P21") (pin "3") (pinfunction "3_3") (pintype "passive"))
      (node (ref "P21") (pin "6") (pinfunction "6_6") (pintype "passive"))
      (node (ref "P6") (pin "3") (pinfunction "3_3") (pintype "passive"))
      (node (ref "P7") (pin "3") (pinfunction "3_3") (pintype "passive"))
      (node (ref "P8") (pin "3") (pinfunction "3_3") (pintype "passive"))
      (node (ref "P9") (pin "3") (pinfunction "3_3") (pintype "passive"))
      (node (ref "R9") (pin "2") (pinfunction "2_2") (pintype "passive"))
    )
    (net (code "62") (name "GND") (class "Default")
      (node (ref "*") (pin "GND") (pinfunction "GND_GND") (pintype "passive"))
      (node (ref "C1") (pin "1") (pinfunction "-_1") (pintype "passive"))
      (node (ref "C13") (pin "2") (pinfunction "2_2") (pintype "passive"))
      (node (ref "C14") (pin "2") (pinfunction "2_2") (pintype "passive"))
      (node (ref "C15") (pin "2") (pinfunction "2_2") (pintype "passive"))
      (node (ref "C16") (pin "1") (pintype "passive"))
      (node (ref "C17") (pin "1") (pintype "passive"))
      (node (ref "C18") (pin "2") (pintype "passive"))
      (node (ref "C19") (pin "1") (pintype "passive"))
      (node (ref "C2") (pin "1") (pinfunction "-_1") (pintype "passive"))
      (node (ref "C20") (pin "1") (pintype "passive"))
      (node (ref "C23") (pin "2") (pintype "passive"))
      (node (ref "C27") (pin "1") (pintype "passive"))
      (node (ref "C29") (pin "2") (pintype "passive"))
      (node (ref "C3") (pin "1") (pinfunction "-_1") (pintype "passive"))
      (node (ref "C30") (pin "1") (pintype "passive"))
      (node (ref "C35") (pin "2") (pinfunction "2_2") (pintype "passive"))
      (node (ref "C36") (pin "2") (pinfunction "2_2") (pintype "passive"))
      (node (ref "C37") (pin "1") (pintype "passive"))
      (node (ref "C4") (pin "1") (pinfunction "-_1") (pintype "passive"))
      (node (ref "C5") (pin "1") (pinfunction "1_1") (pintype "passive"))
      (node (ref "C6") (pin "1") (pinfunction "1_1") (pintype "passive"))
      (node (ref "LED1") (pin "C") (pinfunction "C_C") (pintype "passive"))
      (node (ref "P1") (pin "3") (pinfunction "3_3") (pintype "passive"))
      (node (ref "P11") (pin "4") (pinfunction "GND_4") (pintype "passive"))
      (node (ref "P13") (pin "1") (pinfunction "-_1") (pintype "passive"))
      (node (ref "P14") (pin "2") (pinfunction "2_2") (pintype "passive"))
      (node (ref "P14") (pin "3") (pinfunction "3_3") (pintype "passive"))
      (node (ref "P15") (pin "2") (pinfunction "2_2") (pintype "passive"))
      (node (ref "P16") (pin "4") (pinfunction "4_4") (pintype "passive"))
      (node (ref "P17") (pin "6") (pinfunction "GND_6") (pintype "passive"))
      (node (ref "P19") (pin "2") (pinfunction "2_2") (pintype "passive"))
      (node (ref "P2") (pin "4") (pinfunction "4_4") (pintype "passive"))
      (node (ref "P23") (pin "1") (pinfunction "1_1") (pintype "passive"))
      (node (ref "P24") (pin "1") (pinfunction "1_1") (pintype "passive"))
      (node (ref "P25") (pin "2") (pinfunction "SDA_2") (pintype "passive"))
      (node (ref "P3") (pin "3") (pinfunction "3_3") (pintype "passive"))
      (node (ref "P4") (pin "3") (pinfunction "3_3") (pintype "passive"))
      (node (ref "P5") (pin "1") (pinfunction "GND_1") (pintype "passive"))
      (node (ref "R12") (pin "2") (pinfunction "2_2") (pintype "passive"))
      (node (ref "R14") (pin "2") (pinfunction "2_2") (pintype "passive"))
      (node (ref "R16") (pin "2") (pinfunction "2_2") (pintype "passive"))
      (node (ref "R19") (pin "1") (pinfunction "1_1") (pintype "passive"))
      (node (ref "R2") (pin "1") (pinfunction "1_1") (pintype "passive"))
      (node (ref "R4") (pin "1") (pinfunction "1_1") (pintype "passive"))
      (node (ref "R9") (pin "1") (pinfunction "1_1") (pintype "passive"))
      (node (ref "U1") (pin "9") (pinfunction "VSS_9") (pintype "power_in"))
      (node (ref "U2") (pin "2") (pinfunction "VSS_2") (pintype "passive"))
    )
    (net (code "63") (name "Net-(C5-Pad2)") (class "Default")
      (node (ref "C5") (pin "2") (pinfunction "2_2") (pintype "passive"))
      (node (ref "R5") (pin "1") (pinfunction "1_1") (pintype "passive"))
    )
    (net (code "64") (name "Net-(C6-Pad2)") (class "Default")
      (node (ref "C6") (pin "2") (pinfunction "2_2") (pintype "passive"))
      (node (ref "R6") (pin "1") (pinfunction "1_1") (pintype "passive"))
    )
    (net (code "65") (name "Net-(D1-K)") (class "Default")
      (node (ref "D1") (pin "2") (pinfunction "K_2") (pintype "passive"))
      (node (ref "F1") (pin "1") (pinfunction "1_1") (pintype "passive"))
    )
    (net (code "66") (name "Net-(LED1-PadA)") (class "Default")
      (node (ref "LED1") (pin "A") (pinfunction "A_A") (pintype "passive"))
      (node (ref "R3") (pin "1") (pinfunction "1_1") (pintype "passive"))
    )
    (net (code "67") (name "Net-(P2-Pad2)") (class "Default")
      (node (ref "P2") (pin "2") (pinfunction "2_2") (pintype "passive"))
      (node (ref "R1") (pin "2") (pinfunction "2_2") (pintype "passive"))
    )
    (net (code "68") (name "Net-(P18-Pad2)") (class "Default")
      (node (ref "P18") (pin "2") (pinfunction "2_2") (pintype "passive"))
      (node (ref "R11") (pin "1") (pinfunction "1_1") (pintype "passive"))
      (node (ref "R12") (pin "1") (pinfunction "1_1") (pintype "passive"))
    )
    (net (code "69") (name "Net-(P18-Pad4)") (class "Default")
      (node (ref "P18") (pin "4") (pinfunction "4_4") (pintype "passive"))
      (node (ref "R13") (pin "1") (pinfunction "1_1") (pintype "passive"))
      (node (ref "R14") (pin "1") (pinfunction "1_1") (pintype "passive"))
    )
    (net (code "70") (name "Net-(P18-Pad6)") (class "Default")
      (node (ref "P18") (pin "6") (pinfunction "6_6") (pintype "passive"))
      (node (ref "R15") (pin "1") (pinfunction "1_1") (pintype "passive"))
      (node (ref "R16") (pin "1") (pinfunction "1_1") (pintype "passive"))
    )
    (net (code "71") (name "Net-(P19-Pad1)") (class "Default")
      (node (ref "P19") (pin "1") (pinfunction "1_1") (pintype "passive"))
      (node (ref "R17") (pin "1") (pinfunction "1_1") (pintype "passive"))
    )
    (net (code "72") (name "Net-(Q2-D)") (class "Default")
      (node (ref "P23") (pin "2") (pinfunction "2_2") (pintype "passive"))
      (node (ref "Q2") (pin "3") (pinfunction "D_3") (pintype "passive"))
    )
    (net (code "73") (name "Net-(U1A-OSC1)") (class "Default")
      (node (ref "C35") (pin "1") (pinfunction "1_1") (pintype "passive"))
      (node (ref "Q1") (pin "2") (pinfunction "2_2") (pintype "passive"))
      (node (ref "U1") (pin "8") (pinfunction "OSC1_8") (pintype "passive"))
    )
    (net (code "74") (name "Net-(U1A-OSC2)") (class "Default")
      (node (ref "C36") (pin "1") (pinfunction "1_1") (pintype "passive"))
      (node (ref "Q1") (pin "1") (pinfunction "1_1") (pintype "passive"))
      (node (ref "U1") (pin "7") (pinfunction "OSC2_7") (pintype "output"))
    )
    (net (code "75") (name "Net-(U2-RS)") (class "Default")
      (node (ref "R4") (pin "2") (pinfunction "2_2") (pintype "passive"))
      (node (ref "U2") (pin "8") (pinfunction "RS_8") (pintype "passive"))
    )
    (net (code "76") (name "VCC") (class "Default")
      (node (ref "C1") (pin "2") (pinfunction "+_2") (pintype "passive"))
      (node (ref "C2") (pin "2") (pinfunction "+_2") (pintype "passive"))
      (node (ref "F1") (pin "2") (pinfunction "2_2") (pintype "passive"))
      (node (ref "P14") (pin "1") (pinfunction "1_1") (pintype "passive"))
      (node (ref "Q2") (pin "2") (pinfunction "S_2") (pintype "passive"))
    )
    (net (code "77") (name "unconnected-(*-0(RX0)-PadRX0)") (class "Default")
      (node (ref "*") (pin "RX0") (pinfunction "0(RX0)_RX0") (pintype "passive"))
    )
    (net (code "78") (name "unconnected-(*-1(TX0)-PadTX0)") (class "Default")
      (node (ref "*") (pin "TX0") (pinfunction "1(TX0)_TX0") (pintype "passive"))
    )
    (net (code "79") (name "unconnected-(*-14(TX3)-PadTX3)") (class "Default")
      (node (ref "*") (pin "TX3") (pinfunction "14(TX3)_TX3") (pintype "passive"))
    )
    (net (code "80") (name "unconnected-(*-15(RX3)-PadRX3)") (class "Default")
      (node (ref "*") (pin "RX3") (pinfunction "15(RX3)_RX3") (pintype "passive"))
    )
    (net (code "81") (name "unconnected-(*-Pad3)") (class "Default")
      (node (ref "*") (pin "3") (pinfunction "3_3") (pintype "passive"))
    )
    (net (code "82") (name "unconnected-(*-Pad4)") (class "Default")
      (node (ref "*") (pin "4") (pinfunction "4_4") (pintype "passive"))
    )
    (net (code "83") (name "unconnected-(*-Pad6)") (class "Default")
      (node (ref "*") (pin "6") (pinfunction "6_6") (pintype "passive"))
    )
    (net (code "84") (name "unconnected-(*-Pad7)") (class "Default")
      (node (ref "*") (pin "7") (pinfunction "7_7") (pintype "passive"))
    )
    (net (code "85") (name "unconnected-(*-Pad8)") (class "Default")
      (node (ref "*") (pin "8") (pinfunction "8_8") (pintype "passive"))
    )
    (net (code "86") (name "unconnected-(*-Pad9)") (class "Default")
      (node (ref "*") (pin "9") (pinfunction "9_9") (pintype "passive"))
    )
    (net (code "87") (name "unconnected-(*-Pad10)") (class "Default")
      (node (ref "*") (pin "10") (pinfunction "10_10") (pintype "passive"))
    )
    (net (code "88") (name "unconnected-(*-Pad11)") (class "Default")
      (node (ref "*") (pin "11") (pinfunction "11_11") (pintype "passive"))
    )
    (net (code "89") (name "unconnected-(*-Pad12)") (class "Default")
      (node (ref "*") (pin "12") (pinfunction "12_12") (pintype "passive"))
    )
    (net (code "90") (name "unconnected-(*-Pad13)") (class "Default")
      (node (ref "*") (pin "13") (pinfunction "13_13") (pintype "passive"))
    )
    (net (code "91") (name "unconnected-(*-Pad22)") (class "Default")
      (node (ref "*") (pin "22") (pinfunction "22_22") (pintype "passive"))
    )
    (net (code "92") (name "unconnected-(*-PadA0)") (class "Default")
      (node (ref "*") (pin "A0") (pinfunction "A0_A0") (pintype "passive"))
    )
    (net (code "93") (name "unconnected-(*-PadA1)") (class "Default")
      (node (ref "*") (pin "A1") (pinfunction "A1_A1") (pintype "passive"))
    )
    (net (code "94") (name "unconnected-(*-PadA14)") (class "Default")
      (node (ref "*") (pin "A14") (pinfunction "A14_A14") (pintype "passive"))
    )
    (net (code "95") (name "unconnected-(*-PadA15)") (class "Default")
      (node (ref "*") (pin "A15") (pinfunction "A15_A15") (pintype "passive"))
    )
    (net (code "96") (name "unconnected-(*-PadAREF)") (class "Default")
      (node (ref "*") (pin "AREF") (pinfunction "AREF_AREF") (pintype "passive"))
    )
    (net (code "97") (name "unconnected-(*-PadIOREF)") (class "Default")
      (node (ref "*") (pin "IOREF") (pinfunction "IOREF_IOREF") (pintype "passive"))
    )
    (net (code "98") (name "unconnected-(*-PadVIN)") (class "Default")
      (node (ref "*") (pin "VIN") (pinfunction "VIN_VIN") (pintype "passive"))
    )
    (net (code "99") (name "unconnected-(P5-CD-Pad3)") (class "Default")
      (node (ref "P5") (pin "3") (pinfunction "CD_3") (pintype "passive"))
    )
    (net (code "100") (name "unconnected-(P17-3V-Pad7)") (class "Default")
      (node (ref "P17") (pin "7") (pinfunction "3V_7") (pintype "passive"))
    )
    (net (code "101") (name "unconnected-(U1A-CLKOUT-Pad3)") (class "Default")
      (node (ref "U1") (pin "3") (pinfunction "CLKOUT_3") (pintype "output"))
    )
    (net (code "102") (name "unconnected-(U1A-RX0BF-Pad11)") (class "Default")
      (node (ref "U1") (pin "11") (pinfunction "RX0BF_11") (pintype "output"))
    )
    (net (code "103") (name "unconnected-(U1A-RX1BF-Pad10)") (class "Default")
      (node (ref "U1") (pin "10") (pinfunction "RX1BF_10") (pintype "output"))
    )
    (net (code "104") (name "unconnected-(U1A-TX0RTS-Pad4)") (class "Default")
      (node (ref "U1") (pin "4") (pinfunction "TX0RTS_4") (pintype "passive"))
    )
    (net (code "105") (name "unconnected-(U1A-TX1RTS-Pad5)") (class "Default")
      (node (ref "U1") (pin "5") (pinfunction "TX1RTS_5") (pintype "passive"))
    )
    (net (code "106") (name "unconnected-(U1A-TX2RTS-Pad6)") (class "Default")
      (node (ref "U1") (pin "6") (pinfunction "TX2RTS_6") (pintype "passive"))
    )
    (net (code "107") (name "unconnected-(U2-VREF-Pad5)") (class "Default")
      (node (ref "U2") (pin "5") (pinfunction "VREF_5") (pintype "passive"))
    )
  )
)
